# temp-stellwerk-laser-4-left.net
KiCad netlist of a schematic drawn in EAGLE
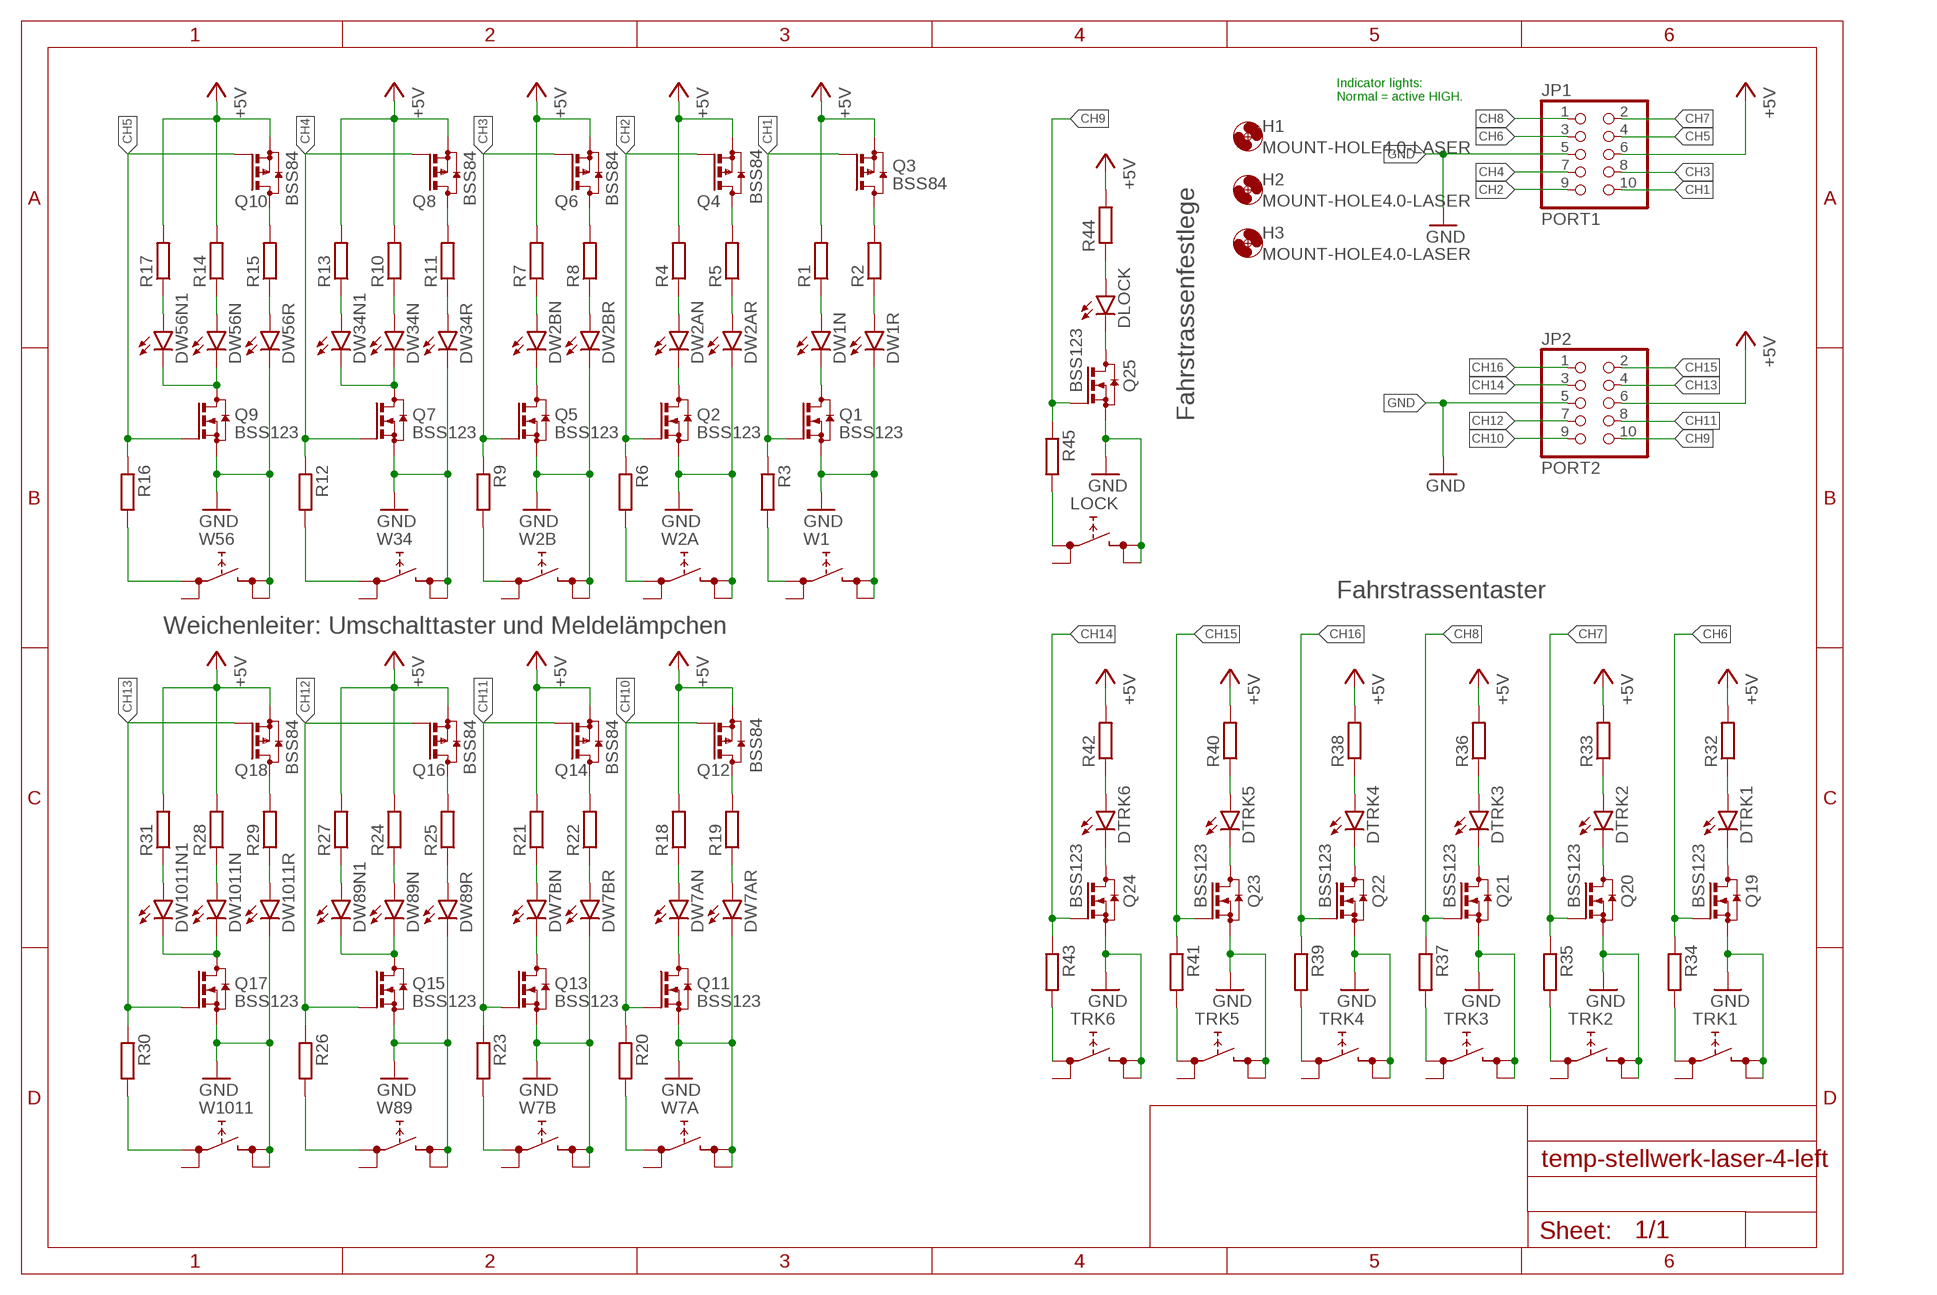
[diagram p0: schematic, sheet 1]

(export (version "E")
  (design (tool "Eeschema 10.0.6"))
  (components
    (comp (ref "DLOCK")
      (value "LEDCHIPLED_0805")
      (footprint "eagle-import:CHIPLED_0805")
      (libsource (lib "eagle-import") (part "LEDCHIPLED_0805"))
    )
    (comp (ref "DTRK1")
      (value "LEDCHIPLED_0805")
      (footprint "eagle-import:CHIPLED_0805")
      (libsource (lib "eagle-import") (part "LEDCHIPLED_0805"))
    )
    (comp (ref "DTRK2")
      (value "LEDCHIPLED_0805")
      (footprint "eagle-import:CHIPLED_0805")
      (libsource (lib "eagle-import") (part "LEDCHIPLED_0805"))
    )
    (comp (ref "DTRK3")
      (value "LEDCHIPLED_0805")
      (footprint "eagle-import:CHIPLED_0805")
      (libsource (lib "eagle-import") (part "LEDCHIPLED_0805"))
    )
    (comp (ref "DTRK4")
      (value "LEDCHIPLED_0805")
      (footprint "eagle-import:CHIPLED_0805")
      (libsource (lib "eagle-import") (part "LEDCHIPLED_0805"))
    )
    (comp (ref "DTRK5")
      (value "LEDCHIPLED_0805")
      (footprint "eagle-import:CHIPLED_0805")
      (libsource (lib "eagle-import") (part "LEDCHIPLED_0805"))
    )
    (comp (ref "DTRK6")
      (value "LEDCHIPLED_0805")
      (footprint "eagle-import:CHIPLED_0805")
      (libsource (lib "eagle-import") (part "LEDCHIPLED_0805"))
    )
    (comp (ref "DW1N")
      (value "LEDCHIPLED_0603")
      (footprint "eagle-import:CHIPLED_0603")
      (libsource (lib "eagle-import") (part "LEDCHIPLED_0603"))
    )
    (comp (ref "DW1R")
      (value "LEDCHIPLED_0603")
      (footprint "eagle-import:CHIPLED_0603")
      (libsource (lib "eagle-import") (part "LEDCHIPLED_0603"))
    )
    (comp (ref "DW2AN")
      (value "LEDCHIPLED_0603")
      (footprint "eagle-import:CHIPLED_0603")
      (libsource (lib "eagle-import") (part "LEDCHIPLED_0603"))
    )
    (comp (ref "DW2AR")
      (value "LEDCHIPLED_0603")
      (footprint "eagle-import:CHIPLED_0603")
      (libsource (lib "eagle-import") (part "LEDCHIPLED_0603"))
    )
    (comp (ref "DW2BN")
      (value "LEDCHIPLED_0805")
      (footprint "eagle-import:CHIPLED_0805")
      (libsource (lib "eagle-import") (part "LEDCHIPLED_0805"))
    )
    (comp (ref "DW2BR")
      (value "LEDCHIPLED_0805")
      (footprint "eagle-import:CHIPLED_0805")
      (libsource (lib "eagle-import") (part "LEDCHIPLED_0805"))
    )
    (comp (ref "DW7AN")
      (value "LEDCHIPLED_0603")
      (footprint "eagle-import:CHIPLED_0603")
      (libsource (lib "eagle-import") (part "LEDCHIPLED_0603"))
    )
    (comp (ref "DW7AR")
      (value "LEDCHIPLED_0603")
      (footprint "eagle-import:CHIPLED_0603")
      (libsource (lib "eagle-import") (part "LEDCHIPLED_0603"))
    )
    (comp (ref "DW7BN")
      (value "LEDCHIPLED_0805")
      (footprint "eagle-import:CHIPLED_0805")
      (libsource (lib "eagle-import") (part "LEDCHIPLED_0805"))
    )
    (comp (ref "DW7BR")
      (value "LEDCHIPLED_0805")
      (footprint "eagle-import:CHIPLED_0805")
      (libsource (lib "eagle-import") (part "LEDCHIPLED_0805"))
    )
    (comp (ref "DW34N")
      (value "LEDCHIPLED_0805")
      (footprint "eagle-import:CHIPLED_0805")
      (libsource (lib "eagle-import") (part "LEDCHIPLED_0805"))
    )
    (comp (ref "DW34N1")
      (value "LEDCHIPLED_0805")
      (footprint "eagle-import:CHIPLED_0805")
      (libsource (lib "eagle-import") (part "LEDCHIPLED_0805"))
    )
    (comp (ref "DW34R")
      (value "LEDCHIPLED_0805")
      (footprint "eagle-import:CHIPLED_0805")
      (libsource (lib "eagle-import") (part "LEDCHIPLED_0805"))
    )
    (comp (ref "DW56N")
      (value "LEDCHIPLED_0805")
      (footprint "eagle-import:CHIPLED_0805")
      (libsource (lib "eagle-import") (part "LEDCHIPLED_0805"))
    )
    (comp (ref "DW56N1")
      (value "LEDCHIPLED_0805")
      (footprint "eagle-import:CHIPLED_0805")
      (libsource (lib "eagle-import") (part "LEDCHIPLED_0805"))
    )
    (comp (ref "DW56R")
      (value "LEDCHIPLED_0805")
      (footprint "eagle-import:CHIPLED_0805")
      (libsource (lib "eagle-import") (part "LEDCHIPLED_0805"))
    )
    (comp (ref "DW89N")
      (value "LEDCHIPLED_0805")
      (footprint "eagle-import:CHIPLED_0805")
      (libsource (lib "eagle-import") (part "LEDCHIPLED_0805"))
    )
    (comp (ref "DW89N1")
      (value "LEDCHIPLED_0805")
      (footprint "eagle-import:CHIPLED_0805")
      (libsource (lib "eagle-import") (part "LEDCHIPLED_0805"))
    )
    (comp (ref "DW89R")
      (value "LEDCHIPLED_0805")
      (footprint "eagle-import:CHIPLED_0805")
      (libsource (lib "eagle-import") (part "LEDCHIPLED_0805"))
    )
    (comp (ref "DW1011N")
      (value "LEDCHIPLED_0805")
      (footprint "eagle-import:CHIPLED_0805")
      (libsource (lib "eagle-import") (part "LEDCHIPLED_0805"))
    )
    (comp (ref "DW1011N1")
      (value "LEDCHIPLED_0805")
      (footprint "eagle-import:CHIPLED_0805")
      (libsource (lib "eagle-import") (part "LEDCHIPLED_0805"))
    )
    (comp (ref "DW1011R")
      (value "LEDCHIPLED_0805")
      (footprint "eagle-import:CHIPLED_0805")
      (libsource (lib "eagle-import") (part "LEDCHIPLED_0805"))
    )
    (comp (ref "H1")
      (value "MOUNT-HOLE4.0-LASER")
      (footprint "eagle-import:MOUNT-HOLE-3.2-4.0-LASER")
      (libsource (lib "eagle-import") (part "MOUNT-HOLE4.0-LASER"))
    )
    (comp (ref "H2")
      (value "MOUNT-HOLE4.0-LASER")
      (footprint "eagle-import:MOUNT-HOLE-3.2-4.0-LASER")
      (libsource (lib "eagle-import") (part "MOUNT-HOLE4.0-LASER"))
    )
    (comp (ref "H3")
      (value "MOUNT-HOLE4.0-LASER")
      (footprint "eagle-import:MOUNT-HOLE-3.2-4.0-LASER")
      (libsource (lib "eagle-import") (part "MOUNT-HOLE4.0-LASER"))
    )
    (comp (ref "JP1")
      (value "PORT1")
      (footprint "eagle-import:CON10M")
      (libsource (lib "eagle-import") (part "PINHD-2X5CN"))
    )
    (comp (ref "JP2")
      (value "PORT2")
      (footprint "eagle-import:CON10M")
      (libsource (lib "eagle-import") (part "PINHD-2X5CN"))
    )
    (comp (ref "LOCK")
      (value "LOCK")
      (footprint "eagle-import:TACTSW-6X6-LASER")
      (libsource (lib "eagle-import") (part "TACTSW-6X6S"))
    )
    (comp (ref "Q1")
      (value "BSS123")
      (footprint "eagle-import:SOT23-NCH")
      (libsource (lib "eagle-import") (part "BSS123"))
    )
    (comp (ref "Q2")
      (value "BSS123")
      (footprint "eagle-import:SOT23-NCH")
      (libsource (lib "eagle-import") (part "BSS123"))
    )
    (comp (ref "Q3")
      (value "BSS84")
      (footprint "eagle-import:SOT23")
      (libsource (lib "eagle-import") (part "BSS84"))
    )
    (comp (ref "Q4")
      (value "BSS84")
      (footprint "eagle-import:SOT23")
      (libsource (lib "eagle-import") (part "BSS84"))
    )
    (comp (ref "Q5")
      (value "BSS123")
      (footprint "eagle-import:SOT23-NCH")
      (libsource (lib "eagle-import") (part "BSS123"))
    )
    (comp (ref "Q6")
      (value "BSS84")
      (footprint "eagle-import:SOT23")
      (libsource (lib "eagle-import") (part "BSS84"))
    )
    (comp (ref "Q7")
      (value "BSS123")
      (footprint "eagle-import:SOT23-NCH")
      (libsource (lib "eagle-import") (part "BSS123"))
    )
    (comp (ref "Q8")
      (value "BSS84")
      (footprint "eagle-import:SOT23")
      (libsource (lib "eagle-import") (part "BSS84"))
    )
    (comp (ref "Q9")
      (value "BSS123")
      (footprint "eagle-import:SOT23-NCH")
      (libsource (lib "eagle-import") (part "BSS123"))
    )
    (comp (ref "Q10")
      (value "BSS84")
      (footprint "eagle-import:SOT23")
      (libsource (lib "eagle-import") (part "BSS84"))
    )
    (comp (ref "Q11")
      (value "BSS123")
      (footprint "eagle-import:SOT23-NCH")
      (libsource (lib "eagle-import") (part "BSS123"))
    )
    (comp (ref "Q12")
      (value "BSS84")
      (footprint "eagle-import:SOT23")
      (libsource (lib "eagle-import") (part "BSS84"))
    )
    (comp (ref "Q13")
      (value "BSS123")
      (footprint "eagle-import:SOT23-NCH")
      (libsource (lib "eagle-import") (part "BSS123"))
    )
    (comp (ref "Q14")
      (value "BSS84")
      (footprint "eagle-import:SOT23")
      (libsource (lib "eagle-import") (part "BSS84"))
    )
    (comp (ref "Q15")
      (value "BSS123")
      (footprint "eagle-import:SOT23-NCH")
      (libsource (lib "eagle-import") (part "BSS123"))
    )
    (comp (ref "Q16")
      (value "BSS84")
      (footprint "eagle-import:SOT23")
      (libsource (lib "eagle-import") (part "BSS84"))
    )
    (comp (ref "Q17")
      (value "BSS123")
      (footprint "eagle-import:SOT23-NCH")
      (libsource (lib "eagle-import") (part "BSS123"))
    )
    (comp (ref "Q18")
      (value "BSS84")
      (footprint "eagle-import:SOT23")
      (libsource (lib "eagle-import") (part "BSS84"))
    )
    (comp (ref "Q19")
      (value "BSS123")
      (footprint "eagle-import:SOT23-NCH")
      (libsource (lib "eagle-import") (part "BSS123"))
    )
    (comp (ref "Q20")
      (value "BSS123")
      (footprint "eagle-import:SOT23-NCH")
      (libsource (lib "eagle-import") (part "BSS123"))
    )
    (comp (ref "Q21")
      (value "BSS123")
      (footprint "eagle-import:SOT23-NCH")
      (libsource (lib "eagle-import") (part "BSS123"))
    )
    (comp (ref "Q22")
      (value "BSS123")
      (footprint "eagle-import:SOT23-NCH")
      (libsource (lib "eagle-import") (part "BSS123"))
    )
    (comp (ref "Q23")
      (value "BSS123")
      (footprint "eagle-import:SOT23-NCH")
      (libsource (lib "eagle-import") (part "BSS123"))
    )
    (comp (ref "Q24")
      (value "BSS123")
      (footprint "eagle-import:SOT23-NCH")
      (libsource (lib "eagle-import") (part "BSS123"))
    )
    (comp (ref "Q25")
      (value "BSS123")
      (footprint "eagle-import:SOT23-NCH")
      (libsource (lib "eagle-import") (part "BSS123"))
    )
    (comp (ref "R1")
      (value "R-EU_R0805")
      (footprint "eagle-import:R0805")
      (libsource (lib "eagle-import") (part "R-EU_R0805"))
    )
    (comp (ref "R2")
      (value "R-EU_R0805")
      (footprint "eagle-import:R0805")
      (libsource (lib "eagle-import") (part "R-EU_R0805"))
    )
    (comp (ref "R3")
      (value "R-EU_R0805")
      (footprint "eagle-import:R0805")
      (libsource (lib "eagle-import") (part "R-EU_R0805"))
    )
    (comp (ref "R4")
      (value "R-EU_R0805")
      (footprint "eagle-import:R0805")
      (libsource (lib "eagle-import") (part "R-EU_R0805"))
    )
    (comp (ref "R5")
      (value "R-EU_R0805")
      (footprint "eagle-import:R0805")
      (libsource (lib "eagle-import") (part "R-EU_R0805"))
    )
    (comp (ref "R6")
      (value "R-EU_R0805")
      (footprint "eagle-import:R0805")
      (libsource (lib "eagle-import") (part "R-EU_R0805"))
    )
    (comp (ref "R7")
      (value "R-EU_R0805")
      (footprint "eagle-import:R0805")
      (libsource (lib "eagle-import") (part "R-EU_R0805"))
    )
    (comp (ref "R8")
      (value "R-EU_R0805")
      (footprint "eagle-import:R0805")
      (libsource (lib "eagle-import") (part "R-EU_R0805"))
    )
    (comp (ref "R9")
      (value "R-EU_R0805")
      (footprint "eagle-import:R0805")
      (libsource (lib "eagle-import") (part "R-EU_R0805"))
    )
    (comp (ref "R10")
      (value "R-EU_R0805")
      (footprint "eagle-import:R0805")
      (libsource (lib "eagle-import") (part "R-EU_R0805"))
    )
    (comp (ref "R11")
      (value "R-EU_R0805")
      (footprint "eagle-import:R0805")
      (libsource (lib "eagle-import") (part "R-EU_R0805"))
    )
    (comp (ref "R12")
      (value "R-EU_R0805")
      (footprint "eagle-import:R0805")
      (libsource (lib "eagle-import") (part "R-EU_R0805"))
    )
    (comp (ref "R13")
      (value "R-EU_R0805")
      (footprint "eagle-import:R0805")
      (libsource (lib "eagle-import") (part "R-EU_R0805"))
    )
    (comp (ref "R14")
      (value "R-EU_R0805")
      (footprint "eagle-import:R0805")
      (libsource (lib "eagle-import") (part "R-EU_R0805"))
    )
    (comp (ref "R15")
      (value "R-EU_R0805")
      (footprint "eagle-import:R0805")
      (libsource (lib "eagle-import") (part "R-EU_R0805"))
    )
    (comp (ref "R16")
      (value "R-EU_R0805")
      (footprint "eagle-import:R0805")
      (libsource (lib "eagle-import") (part "R-EU_R0805"))
    )
    (comp (ref "R17")
      (value "R-EU_R0805")
      (footprint "eagle-import:R0805")
      (libsource (lib "eagle-import") (part "R-EU_R0805"))
    )
    (comp (ref "R18")
      (value "R-EU_R0805")
      (footprint "eagle-import:R0805")
      (libsource (lib "eagle-import") (part "R-EU_R0805"))
    )
    (comp (ref "R19")
      (value "R-EU_R0805")
      (footprint "eagle-import:R0805")
      (libsource (lib "eagle-import") (part "R-EU_R0805"))
    )
    (comp (ref "R20")
      (value "R-EU_R0805")
      (footprint "eagle-import:R0805")
      (libsource (lib "eagle-import") (part "R-EU_R0805"))
    )
    (comp (ref "R21")
      (value "R-EU_R0805")
      (footprint "eagle-import:R0805")
      (libsource (lib "eagle-import") (part "R-EU_R0805"))
    )
    (comp (ref "R22")
      (value "R-EU_R0805")
      (footprint "eagle-import:R0805")
      (libsource (lib "eagle-import") (part "R-EU_R0805"))
    )
    (comp (ref "R23")
      (value "R-EU_R0805")
      (footprint "eagle-import:R0805")
      (libsource (lib "eagle-import") (part "R-EU_R0805"))
    )
    (comp (ref "R24")
      (value "R-EU_R0805")
      (footprint "eagle-import:R0805")
      (libsource (lib "eagle-import") (part "R-EU_R0805"))
    )
    (comp (ref "R25")
      (value "R-EU_R0805")
      (footprint "eagle-import:R0805")
      (libsource (lib "eagle-import") (part "R-EU_R0805"))
    )
    (comp (ref "R26")
      (value "R-EU_R0805")
      (footprint "eagle-import:R0805")
      (libsource (lib "eagle-import") (part "R-EU_R0805"))
    )
    (comp (ref "R27")
      (value "R-EU_R0805")
      (footprint "eagle-import:R0805")
      (libsource (lib "eagle-import") (part "R-EU_R0805"))
    )
    (comp (ref "R28")
      (value "R-EU_R0805")
      (footprint "eagle-import:R0805")
      (libsource (lib "eagle-import") (part "R-EU_R0805"))
    )
    (comp (ref "R29")
      (value "R-EU_R0805")
      (footprint "eagle-import:R0805")
      (libsource (lib "eagle-import") (part "R-EU_R0805"))
    )
    (comp (ref "R30")
      (value "R-EU_R0805")
      (footprint "eagle-import:R0805")
      (libsource (lib "eagle-import") (part "R-EU_R0805"))
    )
    (comp (ref "R31")
      (value "R-EU_R0805")
      (footprint "eagle-import:R0805")
      (libsource (lib "eagle-import") (part "R-EU_R0805"))
    )
    (comp (ref "R32")
      (value "R-EU_R0805")
      (footprint "eagle-import:R0805")
      (libsource (lib "eagle-import") (part "R-EU_R0805"))
    )
    (comp (ref "R33")
      (value "R-EU_R0805")
      (footprint "eagle-import:R0805")
      (libsource (lib "eagle-import") (part "R-EU_R0805"))
    )
    (comp (ref "R34")
      (value "R-EU_R0805")
      (footprint "eagle-import:R0805")
      (libsource (lib "eagle-import") (part "R-EU_R0805"))
    )
    (comp (ref "R35")
      (value "R-EU_R0805")
      (footprint "eagle-import:R0805")
      (libsource (lib "eagle-import") (part "R-EU_R0805"))
    )
    (comp (ref "R36")
      (value "R-EU_R0805")
      (footprint "eagle-import:R0805")
      (libsource (lib "eagle-import") (part "R-EU_R0805"))
    )
    (comp (ref "R37")
      (value "R-EU_R0805")
      (footprint "eagle-import:R0805")
      (libsource (lib "eagle-import") (part "R-EU_R0805"))
    )
    (comp (ref "R38")
      (value "R-EU_R0805")
      (footprint "eagle-import:R0805")
      (libsource (lib "eagle-import") (part "R-EU_R0805"))
    )
    (comp (ref "R39")
      (value "R-EU_R0805")
      (footprint "eagle-import:R0805")
      (libsource (lib "eagle-import") (part "R-EU_R0805"))
    )
    (comp (ref "R40")
      (value "R-EU_R0805")
      (footprint "eagle-import:R0805")
      (libsource (lib "eagle-import") (part "R-EU_R0805"))
    )
    (comp (ref "R41")
      (value "R-EU_R0805")
      (footprint "eagle-import:R0805")
      (libsource (lib "eagle-import") (part "R-EU_R0805"))
    )
    (comp (ref "R42")
      (value "R-EU_R0805")
      (footprint "eagle-import:R0805")
      (libsource (lib "eagle-import") (part "R-EU_R0805"))
    )
    (comp (ref "R43")
      (value "R-EU_R0805")
      (footprint "eagle-import:R0805")
      (libsource (lib "eagle-import") (part "R-EU_R0805"))
    )
    (comp (ref "R44")
      (value "R-EU_R0805")
      (footprint "eagle-import:R0805")
      (libsource (lib "eagle-import") (part "R-EU_R0805"))
    )
    (comp (ref "R45")
      (value "R-EU_R0805")
      (footprint "eagle-import:R0805")
      (libsource (lib "eagle-import") (part "R-EU_R0805"))
    )
    (comp (ref "TRK1")
      (value "TACTSW-6X6S")
      (footprint "eagle-import:TACTSW-6X6-LASER")
      (libsource (lib "eagle-import") (part "TACTSW-6X6S"))
    )
    (comp (ref "TRK2")
      (value "TACTSW-6X6S")
      (footprint "eagle-import:TACTSW-6X6-LASER")
      (libsource (lib "eagle-import") (part "TACTSW-6X6S"))
    )
    (comp (ref "TRK3")
      (value "TACTSW-6X6S")
      (footprint "eagle-import:TACTSW-6X6-LASER")
      (libsource (lib "eagle-import") (part "TACTSW-6X6S"))
    )
    (comp (ref "TRK4")
      (value "TACTSW-6X6S")
      (footprint "eagle-import:TACTSW-6X6-LASER")
      (libsource (lib "eagle-import") (part "TACTSW-6X6S"))
    )
    (comp (ref "TRK5")
      (value "TACTSW-6X6S")
      (footprint "eagle-import:TACTSW-6X6-LASER")
      (libsource (lib "eagle-import") (part "TACTSW-6X6S"))
    )
    (comp (ref "TRK6")
      (value "TACTSW-6X6S")
      (footprint "eagle-import:TACTSW-6X6-LASER")
      (libsource (lib "eagle-import") (part "TACTSW-6X6S"))
    )
    (comp (ref "W1")
      (value "W1")
      (footprint "eagle-import:TACTSW-6X6-LASER")
      (libsource (lib "eagle-import") (part "TACTSW-6X6S"))
    )
    (comp (ref "W2A")
      (value "TACTSW-6X6S")
      (footprint "eagle-import:TACTSW-6X6-LASER")
      (libsource (lib "eagle-import") (part "TACTSW-6X6S"))
    )
    (comp (ref "W2B")
      (value "TACTSW-6X6S")
      (footprint "eagle-import:TACTSW-6X6-LASER")
      (libsource (lib "eagle-import") (part "TACTSW-6X6S"))
    )
    (comp (ref "W7A")
      (value "TACTSW-6X6S")
      (footprint "eagle-import:TACTSW-6X6-LASER")
      (libsource (lib "eagle-import") (part "TACTSW-6X6S"))
    )
    (comp (ref "W7B")
      (value "TACTSW-6X6S")
      (footprint "eagle-import:TACTSW-6X6-LASER")
      (libsource (lib "eagle-import") (part "TACTSW-6X6S"))
    )
    (comp (ref "W34")
      (value "XOVER")
      (footprint "eagle-import:TACTSW-6X6-LASER")
      (libsource (lib "eagle-import") (part "TACTSW-6X6S"))
    )
    (comp (ref "W56")
      (value "XOVER")
      (footprint "eagle-import:TACTSW-6X6-LASER")
      (libsource (lib "eagle-import") (part "TACTSW-6X6S"))
    )
    (comp (ref "W89")
      (value "XOVER")
      (footprint "eagle-import:TACTSW-6X6-LASER")
      (libsource (lib "eagle-import") (part "TACTSW-6X6S"))
    )
    (comp (ref "W1011")
      (value "XOVER")
      (footprint "eagle-import:TACTSW-6X6-LASER")
      (libsource (lib "eagle-import") (part "TACTSW-6X6S"))
    )
  )
  (nets
    (net (code "1") (name "+5V") (class "Default")
      (node (ref "JP1") (pin "6") (pinfunction "6_6") (pintype "passive"))
      (node (ref "JP2") (pin "6") (pinfunction "6_6") (pintype "passive"))
      (node (ref "Q10") (pin "2") (pinfunction "S_2") (pintype "passive"))
      (node (ref "Q12") (pin "2") (pinfunction "S_2") (pintype "passive"))
      (node (ref "Q14") (pin "2") (pinfunction "S_2") (pintype "passive"))
      (node (ref "Q16") (pin "2") (pinfunction "S_2") (pintype "passive"))
      (node (ref "Q18") (pin "2") (pinfunction "S_2") (pintype "passive"))
      (node (ref "Q3") (pin "2") (pinfunction "S_2") (pintype "passive"))
      (node (ref "Q4") (pin "2") (pinfunction "S_2") (pintype "passive"))
      (node (ref "Q6") (pin "2") (pinfunction "S_2") (pintype "passive"))
      (node (ref "Q8") (pin "2") (pinfunction "S_2") (pintype "passive"))
      (node (ref "R1") (pin "2") (pinfunction "2_2") (pintype "passive"))
      (node (ref "R10") (pin "2") (pinfunction "2_2") (pintype "passive"))
      (node (ref "R13") (pin "2") (pinfunction "2_2") (pintype "passive"))
      (node (ref "R14") (pin "2") (pinfunction "2_2") (pintype "passive"))
      (node (ref "R17") (pin "2") (pinfunction "2_2") (pintype "passive"))
      (node (ref "R18") (pin "2") (pinfunction "2_2") (pintype "passive"))
      (node (ref "R21") (pin "2") (pinfunction "2_2") (pintype "passive"))
      (node (ref "R24") (pin "2") (pinfunction "2_2") (pintype "passive"))
      (node (ref "R27") (pin "2") (pinfunction "2_2") (pintype "passive"))
      (node (ref "R28") (pin "2") (pinfunction "2_2") (pintype "passive"))
      (node (ref "R31") (pin "2") (pinfunction "2_2") (pintype "passive"))
      (node (ref "R32") (pin "2") (pinfunction "2_2") (pintype "passive"))
      (node (ref "R33") (pin "2") (pinfunction "2_2") (pintype "passive"))
      (node (ref "R36") (pin "2") (pinfunction "2_2") (pintype "passive"))
      (node (ref "R38") (pin "2") (pinfunction "2_2") (pintype "passive"))
      (node (ref "R4") (pin "2") (pinfunction "2_2") (pintype "passive"))
      (node (ref "R40") (pin "2") (pinfunction "2_2") (pintype "passive"))
      (node (ref "R42") (pin "2") (pinfunction "2_2") (pintype "passive"))
      (node (ref "R44") (pin "2") (pinfunction "2_2") (pintype "passive"))
      (node (ref "R7") (pin "2") (pinfunction "2_2") (pintype "passive"))
    )
    (net (code "2") (name "CH1") (class "Default")
      (node (ref "JP1") (pin "10") (pinfunction "10_10") (pintype "passive"))
      (node (ref "Q1") (pin "1") (pinfunction "G_1") (pintype "passive"))
      (node (ref "Q3") (pin "1") (pinfunction "G_1") (pintype "passive"))
      (node (ref "R3") (pin "1") (pinfunction "1_1") (pintype "passive"))
    )
    (net (code "3") (name "CH2") (class "Default")
      (node (ref "JP1") (pin "9") (pinfunction "9_9") (pintype "passive"))
      (node (ref "Q2") (pin "1") (pinfunction "G_1") (pintype "passive"))
      (node (ref "Q4") (pin "1") (pinfunction "G_1") (pintype "passive"))
      (node (ref "R6") (pin "1") (pinfunction "1_1") (pintype "passive"))
    )
    (net (code "4") (name "CH3") (class "Default")
      (node (ref "JP1") (pin "8") (pinfunction "8_8") (pintype "passive"))
      (node (ref "Q5") (pin "1") (pinfunction "G_1") (pintype "passive"))
      (node (ref "Q6") (pin "1") (pinfunction "G_1") (pintype "passive"))
      (node (ref "R9") (pin "1") (pinfunction "1_1") (pintype "passive"))
    )
    (net (code "5") (name "CH4") (class "Default")
      (node (ref "JP1") (pin "7") (pinfunction "7_7") (pintype "passive"))
      (node (ref "Q7") (pin "1") (pinfunction "G_1") (pintype "passive"))
      (node (ref "Q8") (pin "1") (pinfunction "G_1") (pintype "passive"))
      (node (ref "R12") (pin "1") (pinfunction "1_1") (pintype "passive"))
    )
    (net (code "6") (name "CH5") (class "Default")
      (node (ref "JP1") (pin "4") (pinfunction "4_4") (pintype "passive"))
      (node (ref "Q10") (pin "1") (pinfunction "G_1") (pintype "passive"))
      (node (ref "Q9") (pin "1") (pinfunction "G_1") (pintype "passive"))
      (node (ref "R16") (pin "1") (pinfunction "1_1") (pintype "passive"))
    )
    (net (code "7") (name "CH6") (class "Default")
      (node (ref "JP1") (pin "3") (pinfunction "3_3") (pintype "passive"))
      (node (ref "Q19") (pin "1") (pinfunction "G_1") (pintype "passive"))
      (node (ref "R34") (pin "1") (pinfunction "1_1") (pintype "passive"))
    )
    (net (code "8") (name "CH7") (class "Default")
      (node (ref "JP1") (pin "2") (pinfunction "2_2") (pintype "passive"))
      (node (ref "Q20") (pin "1") (pinfunction "G_1") (pintype "passive"))
      (node (ref "R35") (pin "1") (pinfunction "1_1") (pintype "passive"))
    )
    (net (code "9") (name "CH8") (class "Default")
      (node (ref "JP1") (pin "1") (pinfunction "1_1") (pintype "passive"))
      (node (ref "Q21") (pin "1") (pinfunction "G_1") (pintype "passive"))
      (node (ref "R37") (pin "1") (pinfunction "1_1") (pintype "passive"))
    )
    (net (code "10") (name "CH9") (class "Default")
      (node (ref "JP2") (pin "10") (pinfunction "10_10") (pintype "passive"))
      (node (ref "Q25") (pin "1") (pinfunction "G_1") (pintype "passive"))
      (node (ref "R45") (pin "1") (pinfunction "1_1") (pintype "passive"))
    )
    (net (code "11") (name "CH10") (class "Default")
      (node (ref "JP2") (pin "9") (pinfunction "9_9") (pintype "passive"))
      (node (ref "Q11") (pin "1") (pinfunction "G_1") (pintype "passive"))
      (node (ref "Q12") (pin "1") (pinfunction "G_1") (pintype "passive"))
      (node (ref "R20") (pin "1") (pinfunction "1_1") (pintype "passive"))
    )
    (net (code "12") (name "CH11") (class "Default")
      (node (ref "JP2") (pin "8") (pinfunction "8_8") (pintype "passive"))
      (node (ref "Q13") (pin "1") (pinfunction "G_1") (pintype "passive"))
      (node (ref "Q14") (pin "1") (pinfunction "G_1") (pintype "passive"))
      (node (ref "R23") (pin "1") (pinfunction "1_1") (pintype "passive"))
    )
    (net (code "13") (name "CH12") (class "Default")
      (node (ref "JP2") (pin "7") (pinfunction "7_7") (pintype "passive"))
      (node (ref "Q15") (pin "1") (pinfunction "G_1") (pintype "passive"))
      (node (ref "Q16") (pin "1") (pinfunction "G_1") (pintype "passive"))
      (node (ref "R26") (pin "1") (pinfunction "1_1") (pintype "passive"))
    )
    (net (code "14") (name "CH13") (class "Default")
      (node (ref "JP2") (pin "4") (pinfunction "4_4") (pintype "passive"))
      (node (ref "Q17") (pin "1") (pinfunction "G_1") (pintype "passive"))
      (node (ref "Q18") (pin "1") (pinfunction "G_1") (pintype "passive"))
      (node (ref "R30") (pin "1") (pinfunction "1_1") (pintype "passive"))
    )
    (net (code "15") (name "CH14") (class "Default")
      (node (ref "JP2") (pin "3") (pinfunction "3_3") (pintype "passive"))
      (node (ref "Q24") (pin "1") (pinfunction "G_1") (pintype "passive"))
      (node (ref "R43") (pin "1") (pinfunction "1_1") (pintype "passive"))
    )
    (net (code "16") (name "CH15") (class "Default")
      (node (ref "JP2") (pin "2") (pinfunction "2_2") (pintype "passive"))
      (node (ref "Q23") (pin "1") (pinfunction "G_1") (pintype "passive"))
      (node (ref "R41") (pin "1") (pinfunction "1_1") (pintype "passive"))
    )
    (net (code "17") (name "CH16") (class "Default")
      (node (ref "JP2") (pin "1") (pinfunction "1_1") (pintype "passive"))
      (node (ref "Q22") (pin "1") (pinfunction "G_1") (pintype "passive"))
      (node (ref "R39") (pin "1") (pinfunction "1_1") (pintype "passive"))
    )
    (net (code "18") (name "GND") (class "Default")
      (node (ref "DW1011R") (pin "C") (pinfunction "C_C") (pintype "passive"))
      (node (ref "DW1R") (pin "C") (pinfunction "C_C") (pintype "passive"))
      (node (ref "DW2AR") (pin "C") (pinfunction "C_C") (pintype "passive"))
      (node (ref "DW2BR") (pin "C") (pinfunction "C_C") (pintype "passive"))
      (node (ref "DW34R") (pin "C") (pinfunction "C_C") (pintype "passive"))
      (node (ref "DW56R") (pin "C") (pinfunction "C_C") (pintype "passive"))
      (node (ref "DW7AR") (pin "C") (pinfunction "C_C") (pintype "passive"))
      (node (ref "DW7BR") (pin "C") (pinfunction "C_C") (pintype "passive"))
      (node (ref "DW89R") (pin "C") (pinfunction "C_C") (pintype "passive"))
      (node (ref "JP1") (pin "5") (pinfunction "5_5") (pintype "passive"))
      (node (ref "JP2") (pin "5") (pinfunction "5_5") (pintype "passive"))
      (node (ref "LOCK") (pin "3") (pinfunction "2.1_3") (pintype "passive"))
      (node (ref "LOCK") (pin "4") (pinfunction "2.2_4") (pintype "passive"))
      (node (ref "Q1") (pin "2") (pinfunction "S_2") (pintype "passive"))
      (node (ref "Q11") (pin "2") (pinfunction "S_2") (pintype "passive"))
      (node (ref "Q13") (pin "2") (pinfunction "S_2") (pintype "passive"))
      (node (ref "Q15") (pin "2") (pinfunction "S_2") (pintype "passive"))
      (node (ref "Q17") (pin "2") (pinfunction "S_2") (pintype "passive"))
      (node (ref "Q19") (pin "2") (pinfunction "S_2") (pintype "passive"))
      (node (ref "Q2") (pin "2") (pinfunction "S_2") (pintype "passive"))
      (node (ref "Q20") (pin "2") (pinfunction "S_2") (pintype "passive"))
      (node (ref "Q21") (pin "2") (pinfunction "S_2") (pintype "passive"))
      (node (ref "Q22") (pin "2") (pinfunction "S_2") (pintype "passive"))
      (node (ref "Q23") (pin "2") (pinfunction "S_2") (pintype "passive"))
      (node (ref "Q24") (pin "2") (pinfunction "S_2") (pintype "passive"))
      (node (ref "Q25") (pin "2") (pinfunction "S_2") (pintype "passive"))
      (node (ref "Q5") (pin "2") (pinfunction "S_2") (pintype "passive"))
      (node (ref "Q7") (pin "2") (pinfunction "S_2") (pintype "passive"))
      (node (ref "Q9") (pin "2") (pinfunction "S_2") (pintype "passive"))
      (node (ref "TRK1") (pin "3") (pinfunction "2.1_3") (pintype "passive"))
      (node (ref "TRK1") (pin "4") (pinfunction "2.2_4") (pintype "passive"))
      (node (ref "TRK2") (pin "3") (pinfunction "2.1_3") (pintype "passive"))
      (node (ref "TRK2") (pin "4") (pinfunction "2.2_4") (pintype "passive"))
      (node (ref "TRK3") (pin "3") (pinfunction "2.1_3") (pintype "passive"))
      (node (ref "TRK3") (pin "4") (pinfunction "2.2_4") (pintype "passive"))
      (node (ref "TRK4") (pin "3") (pinfunction "2.1_3") (pintype "passive"))
      (node (ref "TRK4") (pin "4") (pinfunction "2.2_4") (pintype "passive"))
      (node (ref "TRK5") (pin "3") (pinfunction "2.1_3") (pintype "passive"))
      (node (ref "TRK5") (pin "4") (pinfunction "2.2_4") (pintype "passive"))
      (node (ref "TRK6") (pin "3") (pinfunction "2.1_3") (pintype "passive"))
      (node (ref "TRK6") (pin "4") (pinfunction "2.2_4") (pintype "passive"))
      (node (ref "W1") (pin "3") (pinfunction "2.1_3") (pintype "passive"))
      (node (ref "W1") (pin "4") (pinfunction "2.2_4") (pintype "passive"))
      (node (ref "W1011") (pin "3") (pinfunction "2.1_3") (pintype "passive"))
      (node (ref "W1011") (pin "4") (pinfunction "2.2_4") (pintype "passive"))
      (node (ref "W2A") (pin "3") (pinfunction "2.1_3") (pintype "passive"))
      (node (ref "W2A") (pin "4") (pinfunction "2.2_4") (pintype "passive"))
      (node (ref "W2B") (pin "3") (pinfunction "2.1_3") (pintype "passive"))
      (node (ref "W2B") (pin "4") (pinfunction "2.2_4") (pintype "passive"))
      (node (ref "W34") (pin "3") (pinfunction "2.1_3") (pintype "passive"))
      (node (ref "W34") (pin "4") (pinfunction "2.2_4") (pintype "passive"))
      (node (ref "W56") (pin "3") (pinfunction "2.1_3") (pintype "passive"))
      (node (ref "W56") (pin "4") (pinfunction "2.2_4") (pintype "passive"))
      (node (ref "W7A") (pin "3") (pinfunction "2.1_3") (pintype "passive"))
      (node (ref "W7A") (pin "4") (pinfunction "2.2_4") (pintype "passive"))
      (node (ref "W7B") (pin "3") (pinfunction "2.1_3") (pintype "passive"))
      (node (ref "W7B") (pin "4") (pinfunction "2.2_4") (pintype "passive"))
      (node (ref "W89") (pin "3") (pinfunction "2.1_3") (pintype "passive"))
      (node (ref "W89") (pin "4") (pinfunction "2.2_4") (pintype "passive"))
    )
    (net (code "19") (name "Net-(DLOCK-PadA)") (class "Default")
      (node (ref "DLOCK") (pin "A") (pinfunction "A_A") (pintype "passive"))
      (node (ref "R44") (pin "1") (pinfunction "1_1") (pintype "passive"))
    )
    (net (code "20") (name "Net-(DTRK1-PadA)") (class "Default")
      (node (ref "DTRK1") (pin "A") (pinfunction "A_A") (pintype "passive"))
      (node (ref "R32") (pin "1") (pinfunction "1_1") (pintype "passive"))
    )
    (net (code "21") (name "Net-(DTRK2-PadA)") (class "Default")
      (node (ref "DTRK2") (pin "A") (pinfunction "A_A") (pintype "passive"))
      (node (ref "R33") (pin "1") (pinfunction "1_1") (pintype "passive"))
    )
    (net (code "22") (name "Net-(DTRK3-PadA)") (class "Default")
      (node (ref "DTRK3") (pin "A") (pinfunction "A_A") (pintype "passive"))
      (node (ref "R36") (pin "1") (pinfunction "1_1") (pintype "passive"))
    )
    (net (code "23") (name "Net-(DTRK4-PadA)") (class "Default")
      (node (ref "DTRK4") (pin "A") (pinfunction "A_A") (pintype "passive"))
      (node (ref "R38") (pin "1") (pinfunction "1_1") (pintype "passive"))
    )
    (net (code "24") (name "Net-(DTRK5-PadA)") (class "Default")
      (node (ref "DTRK5") (pin "A") (pinfunction "A_A") (pintype "passive"))
      (node (ref "R40") (pin "1") (pinfunction "1_1") (pintype "passive"))
    )
    (net (code "25") (name "Net-(DTRK6-PadA)") (class "Default")
      (node (ref "DTRK6") (pin "A") (pinfunction "A_A") (pintype "passive"))
      (node (ref "R42") (pin "1") (pinfunction "1_1") (pintype "passive"))
    )
    (net (code "26") (name "Net-(DW1N-PadA)") (class "Default")
      (node (ref "DW1N") (pin "A") (pinfunction "A_A") (pintype "passive"))
      (node (ref "R1") (pin "1") (pinfunction "1_1") (pintype "passive"))
    )
    (net (code "27") (name "Net-(DW1R-PadA)") (class "Default")
      (node (ref "DW1R") (pin "A") (pinfunction "A_A") (pintype "passive"))
      (node (ref "R2") (pin "1") (pinfunction "1_1") (pintype "passive"))
    )
    (net (code "28") (name "Net-(DW2AN-PadA)") (class "Default")
      (node (ref "DW2AN") (pin "A") (pinfunction "A_A") (pintype "passive"))
      (node (ref "R4") (pin "1") (pinfunction "1_1") (pintype "passive"))
    )
    (net (code "29") (name "Net-(DW2AR-PadA)") (class "Default")
      (node (ref "DW2AR") (pin "A") (pinfunction "A_A") (pintype "passive"))
      (node (ref "R5") (pin "1") (pinfunction "1_1") (pintype "passive"))
    )
    (net (code "30") (name "Net-(DW2BN-PadA)") (class "Default")
      (node (ref "DW2BN") (pin "A") (pinfunction "A_A") (pintype "passive"))
      (node (ref "R7") (pin "1") (pinfunction "1_1") (pintype "passive"))
    )
    (net (code "31") (name "Net-(DW2BR-PadA)") (class "Default")
      (node (ref "DW2BR") (pin "A") (pinfunction "A_A") (pintype "passive"))
      (node (ref "R8") (pin "1") (pinfunction "1_1") (pintype "passive"))
    )
    (net (code "32") (name "Net-(DW7AN-PadA)") (class "Default")
      (node (ref "DW7AN") (pin "A") (pinfunction "A_A") (pintype "passive"))
      (node (ref "R18") (pin "1") (pinfunction "1_1") (pintype "passive"))
    )
    (net (code "33") (name "Net-(DW7AR-PadA)") (class "Default")
      (node (ref "DW7AR") (pin "A") (pinfunction "A_A") (pintype "passive"))
      (node (ref "R19") (pin "1") (pinfunction "1_1") (pintype "passive"))
    )
    (net (code "34") (name "Net-(DW7BN-PadA)") (class "Default")
      (node (ref "DW7BN") (pin "A") (pinfunction "A_A") (pintype "passive"))
      (node (ref "R21") (pin "1") (pinfunction "1_1") (pintype "passive"))
    )
    (net (code "35") (name "Net-(DW7BR-PadA)") (class "Default")
      (node (ref "DW7BR") (pin "A") (pinfunction "A_A") (pintype "passive"))
      (node (ref "R22") (pin "1") (pinfunction "1_1") (pintype "passive"))
    )
    (net (code "36") (name "Net-(DW34N-PadA)") (class "Default")
      (node (ref "DW34N") (pin "A") (pinfunction "A_A") (pintype "passive"))
      (node (ref "R10") (pin "1") (pinfunction "1_1") (pintype "passive"))
    )
    (net (code "37") (name "Net-(DW34N1-PadA)") (class "Default")
      (node (ref "DW34N1") (pin "A") (pinfunction "A_A") (pintype "passive"))
      (node (ref "R13") (pin "1") (pinfunction "1_1") (pintype "passive"))
    )
    (net (code "38") (name "Net-(DW34R-PadA)") (class "Default")
      (node (ref "DW34R") (pin "A") (pinfunction "A_A") (pintype "passive"))
      (node (ref "R11") (pin "1") (pinfunction "1_1") (pintype "passive"))
    )
    (net (code "39") (name "Net-(DW56N-PadA)") (class "Default")
      (node (ref "DW56N") (pin "A") (pinfunction "A_A") (pintype "passive"))
      (node (ref "R14") (pin "1") (pinfunction "1_1") (pintype "passive"))
    )
    (net (code "40") (name "Net-(DW56N1-PadA)") (class "Default")
      (node (ref "DW56N1") (pin "A") (pinfunction "A_A") (pintype "passive"))
      (node (ref "R17") (pin "1") (pinfunction "1_1") (pintype "passive"))
    )
    (net (code "41") (name "Net-(DW56R-PadA)") (class "Default")
      (node (ref "DW56R") (pin "A") (pinfunction "A_A") (pintype "passive"))
      (node (ref "R15") (pin "1") (pinfunction "1_1") (pintype "passive"))
    )
    (net (code "42") (name "Net-(DW89N-PadA)") (class "Default")
      (node (ref "DW89N") (pin "A") (pinfunction "A_A") (pintype "passive"))
      (node (ref "R24") (pin "1") (pinfunction "1_1") (pintype "passive"))
    )
    (net (code "43") (name "Net-(DW89N1-PadA)") (class "Default")
      (node (ref "DW89N1") (pin "A") (pinfunction "A_A") (pintype "passive"))
      (node (ref "R27") (pin "1") (pinfunction "1_1") (pintype "passive"))
    )
    (net (code "44") (name "Net-(DW89R-PadA)") (class "Default")
      (node (ref "DW89R") (pin "A") (pinfunction "A_A") (pintype "passive"))
      (node (ref "R25") (pin "1") (pinfunction "1_1") (pintype "passive"))
    )
    (net (code "45") (name "Net-(DW1011N-PadA)") (class "Default")
      (node (ref "DW1011N") (pin "A") (pinfunction "A_A") (pintype "passive"))
      (node (ref "R28") (pin "1") (pinfunction "1_1") (pintype "passive"))
    )
    (net (code "46") (name "Net-(DW1011N1-PadA)") (class "Default")
      (node (ref "DW1011N1") (pin "A") (pinfunction "A_A") (pintype "passive"))
      (node (ref "R31") (pin "1") (pinfunction "1_1") (pintype "passive"))
    )
    (net (code "47") (name "Net-(DW1011R-PadA)") (class "Default")
      (node (ref "DW1011R") (pin "A") (pinfunction "A_A") (pintype "passive"))
      (node (ref "R29") (pin "1") (pinfunction "1_1") (pintype "passive"))
    )
    (net (code "48") (name "Net-(LOCK-1.1)") (class "Default")
      (node (ref "LOCK") (pin "1") (pinfunction "1.1_1") (pintype "passive"))
      (node (ref "R45") (pin "2") (pinfunction "2_2") (pintype "passive"))
    )
    (net (code "49") (name "Net-(Q1-D)") (class "Default")
      (node (ref "DW1N") (pin "C") (pinfunction "C_C") (pintype "passive"))
      (node (ref "Q1") (pin "3") (pinfunction "D_3") (pintype "passive"))
    )
    (net (code "50") (name "Net-(Q2-D)") (class "Default")
      (node (ref "DW2AN") (pin "C") (pinfunction "C_C") (pintype "passive"))
      (node (ref "Q2") (pin "3") (pinfunction "D_3") (pintype "passive"))
    )
    (net (code "51") (name "Net-(Q3-D)") (class "Default")
      (node (ref "Q3") (pin "3") (pinfunction "D_3") (pintype "passive"))
      (node (ref "R2") (pin "2") (pinfunction "2_2") (pintype "passive"))
    )
    (net (code "52") (name "Net-(Q4-D)") (class "Default")
      (node (ref "Q4") (pin "3") (pinfunction "D_3") (pintype "passive"))
      (node (ref "R5") (pin "2") (pinfunction "2_2") (pintype "passive"))
    )
    (net (code "53") (name "Net-(Q5-D)") (class "Default")
      (node (ref "DW2BN") (pin "C") (pinfunction "C_C") (pintype "passive"))
      (node (ref "Q5") (pin "3") (pinfunction "D_3") (pintype "passive"))
    )
    (net (code "54") (name "Net-(Q6-D)") (class "Default")
      (node (ref "Q6") (pin "3") (pinfunction "D_3") (pintype "passive"))
      (node (ref "R8") (pin "2") (pinfunction "2_2") (pintype "passive"))
    )
    (net (code "55") (name "Net-(Q7-D)") (class "Default")
      (node (ref "DW34N") (pin "C") (pinfunction "C_C") (pintype "passive"))
      (node (ref "DW34N1") (pin "C") (pinfunction "C_C") (pintype "passive"))
      (node (ref "Q7") (pin "3") (pinfunction "D_3") (pintype "passive"))
    )
    (net (code "56") (name "Net-(Q8-D)") (class "Default")
      (node (ref "Q8") (pin "3") (pinfunction "D_3") (pintype "passive"))
      (node (ref "R11") (pin "2") (pinfunction "2_2") (pintype "passive"))
    )
    (net (code "57") (name "Net-(Q9-D)") (class "Default")
      (node (ref "DW56N") (pin "C") (pinfunction "C_C") (pintype "passive"))
      (node (ref "DW56N1") (pin "C") (pinfunction "C_C") (pintype "passive"))
      (node (ref "Q9") (pin "3") (pinfunction "D_3") (pintype "passive"))
    )
    (net (code "58") (name "Net-(Q10-D)") (class "Default")
      (node (ref "Q10") (pin "3") (pinfunction "D_3") (pintype "passive"))
      (node (ref "R15") (pin "2") (pinfunction "2_2") (pintype "passive"))
    )
    (net (code "59") (name "Net-(Q11-D)") (class "Default")
      (node (ref "DW7AN") (pin "C") (pinfunction "C_C") (pintype "passive"))
      (node (ref "Q11") (pin "3") (pinfunction "D_3") (pintype "passive"))
    )
    (net (code "60") (name "Net-(Q12-D)") (class "Default")
      (node (ref "Q12") (pin "3") (pinfunction "D_3") (pintype "passive"))
      (node (ref "R19") (pin "2") (pinfunction "2_2") (pintype "passive"))
    )
    (net (code "61") (name "Net-(Q13-D)") (class "Default")
      (node (ref "DW7BN") (pin "C") (pinfunction "C_C") (pintype "passive"))
      (node (ref "Q13") (pin "3") (pinfunction "D_3") (pintype "passive"))
    )
    (net (code "62") (name "Net-(Q14-D)") (class "Default")
      (node (ref "Q14") (pin "3") (pinfunction "D_3") (pintype "passive"))
      (node (ref "R22") (pin "2") (pinfunction "2_2") (pintype "passive"))
    )
    (net (code "63") (name "Net-(Q15-D)") (class "Default")
      (node (ref "DW89N") (pin "C") (pinfunction "C_C") (pintype "passive"))
      (node (ref "DW89N1") (pin "C") (pinfunction "C_C") (pintype "passive"))
      (node (ref "Q15") (pin "3") (pinfunction "D_3") (pintype "passive"))
    )
    (net (code "64") (name "Net-(Q16-D)") (class "Default")
      (node (ref "Q16") (pin "3") (pinfunction "D_3") (pintype "passive"))
      (node (ref "R25") (pin "2") (pinfunction "2_2") (pintype "passive"))
    )
    (net (code "65") (name "Net-(Q17-D)") (class "Default")
      (node (ref "DW1011N") (pin "C") (pinfunction "C_C") (pintype "passive"))
      (node (ref "DW1011N1") (pin "C") (pinfunction "C_C") (pintype "passive"))
      (node (ref "Q17") (pin "3") (pinfunction "D_3") (pintype "passive"))
    )
    (net (code "66") (name "Net-(Q18-D)") (class "Default")
      (node (ref "Q18") (pin "3") (pinfunction "D_3") (pintype "passive"))
      (node (ref "R29") (pin "2") (pinfunction "2_2") (pintype "passive"))
    )
    (net (code "67") (name "Net-(Q19-D)") (class "Default")
      (node (ref "DTRK1") (pin "C") (pinfunction "C_C") (pintype "passive"))
      (node (ref "Q19") (pin "3") (pinfunction "D_3") (pintype "passive"))
    )
    (net (code "68") (name "Net-(Q20-D)") (class "Default")
      (node (ref "DTRK2") (pin "C") (pinfunction "C_C") (pintype "passive"))
      (node (ref "Q20") (pin "3") (pinfunction "D_3") (pintype "passive"))
    )
    (net (code "69") (name "Net-(Q21-D)") (class "Default")
      (node (ref "DTRK3") (pin "C") (pinfunction "C_C") (pintype "passive"))
      (node (ref "Q21") (pin "3") (pinfunction "D_3") (pintype "passive"))
    )
    (net (code "70") (name "Net-(Q22-D)") (class "Default")
      (node (ref "DTRK4") (pin "C") (pinfunction "C_C") (pintype "passive"))
      (node (ref "Q22") (pin "3") (pinfunction "D_3") (pintype "passive"))
    )
    (net (code "71") (name "Net-(Q23-D)") (class "Default")
      (node (ref "DTRK5") (pin "C") (pinfunction "C_C") (pintype "passive"))
      (node (ref "Q23") (pin "3") (pinfunction "D_3") (pintype "passive"))
    )
    (net (code "72") (name "Net-(Q24-D)") (class "Default")
      (node (ref "DTRK6") (pin "C") (pinfunction "C_C") (pintype "passive"))
      (node (ref "Q24") (pin "3") (pinfunction "D_3") (pintype "passive"))
    )
    (net (code "73") (name "Net-(Q25-D)") (class "Default")
      (node (ref "DLOCK") (pin "C") (pinfunction "C_C") (pintype "passive"))
      (node (ref "Q25") (pin "3") (pinfunction "D_3") (pintype "passive"))
    )
    (net (code "74") (name "Net-(TRK1-1.1)") (class "Default")
      (node (ref "R34") (pin "2") (pinfunction "2_2") (pintype "passive"))
      (node (ref "TRK1") (pin "1") (pinfunction "1.1_1") (pintype "passive"))
    )
    (net (code "75") (name "Net-(TRK2-1.1)") (class "Default")
      (node (ref "R35") (pin "2") (pinfunction "2_2") (pintype "passive"))
      (node (ref "TRK2") (pin "1") (pinfunction "1.1_1") (pintype "passive"))
    )
    (net (code "76") (name "Net-(TRK3-1.1)") (class "Default")
      (node (ref "R37") (pin "2") (pinfunction "2_2") (pintype "passive"))
      (node (ref "TRK3") (pin "1") (pinfunction "1.1_1") (pintype "passive"))
    )
    (net (code "77") (name "Net-(TRK4-1.1)") (class "Default")
      (node (ref "R39") (pin "2") (pinfunction "2_2") (pintype "passive"))
      (node (ref "TRK4") (pin "1") (pinfunction "1.1_1") (pintype "passive"))
    )
    (net (code "78") (name "Net-(TRK5-1.1)") (class "Default")
      (node (ref "R41") (pin "2") (pinfunction "2_2") (pintype "passive"))
      (node (ref "TRK5") (pin "1") (pinfunction "1.1_1") (pintype "passive"))
    )
    (net (code "79") (name "Net-(TRK6-1.1)") (class "Default")
      (node (ref "R43") (pin "2") (pinfunction "2_2") (pintype "passive"))
      (node (ref "TRK6") (pin "1") (pinfunction "1.1_1") (pintype "passive"))
    )
    (net (code "80") (name "Net-(W1-1.1)") (class "Default")
      (node (ref "R3") (pin "2") (pinfunction "2_2") (pintype "passive"))
      (node (ref "W1") (pin "1") (pinfunction "1.1_1") (pintype "passive"))
    )
    (net (code "81") (name "Net-(W2A-1.1)") (class "Default")
      (node (ref "R6") (pin "2") (pinfunction "2_2") (pintype "passive"))
      (node (ref "W2A") (pin "1") (pinfunction "1.1_1") (pintype "passive"))
    )
    (net (code "82") (name "Net-(W2B-1.1)") (class "Default")
      (node (ref "R9") (pin "2") (pinfunction "2_2") (pintype "passive"))
      (node (ref "W2B") (pin "1") (pinfunction "1.1_1") (pintype "passive"))
    )
    (net (code "83") (name "Net-(W7A-1.1)") (class "Default")
      (node (ref "R20") (pin "2") (pinfunction "2_2") (pintype "passive"))
      (node (ref "W7A") (pin "1") (pinfunction "1.1_1") (pintype "passive"))
    )
    (net (code "84") (name "Net-(W7B-1.1)") (class "Default")
      (node (ref "R23") (pin "2") (pinfunction "2_2") (pintype "passive"))
      (node (ref "W7B") (pin "1") (pinfunction "1.1_1") (pintype "passive"))
    )
    (net (code "85") (name "Net-(W34-1.1)") (class "Default")
      (node (ref "R12") (pin "2") (pinfunction "2_2") (pintype "passive"))
      (node (ref "W34") (pin "1") (pinfunction "1.1_1") (pintype "passive"))
    )
    (net (code "86") (name "Net-(W56-1.1)") (class "Default")
      (node (ref "R16") (pin "2") (pinfunction "2_2") (pintype "passive"))
      (node (ref "W56") (pin "1") (pinfunction "1.1_1") (pintype "passive"))
    )
    (net (code "87") (name "Net-(W89-1.1)") (class "Default")
      (node (ref "R26") (pin "2") (pinfunction "2_2") (pintype "passive"))
      (node (ref "W89") (pin "1") (pinfunction "1.1_1") (pintype "passive"))
    )
    (net (code "88") (name "Net-(W1011-1.1)") (class "Default")
      (node (ref "R30") (pin "2") (pinfunction "2_2") (pintype "passive"))
      (node (ref "W1011") (pin "1") (pinfunction "1.1_1") (pintype "passive"))
    )
    (net (code "89") (name "unconnected-(LOCK-1.2-Pad2)") (class "Default")
      (node (ref "LOCK") (pin "2") (pinfunction "1.2_2") (pintype "passive"))
    )
    (net (code "90") (name "unconnected-(TRK1-1.2-Pad2)") (class "Default")
      (node (ref "TRK1") (pin "2") (pinfunction "1.2_2") (pintype "passive"))
    )
    (net (code "91") (name "unconnected-(TRK2-1.2-Pad2)") (class "Default")
      (node (ref "TRK2") (pin "2") (pinfunction "1.2_2") (pintype "passive"))
    )
    (net (code "92") (name "unconnected-(TRK3-1.2-Pad2)") (class "Default")
      (node (ref "TRK3") (pin "2") (pinfunction "1.2_2") (pintype "passive"))
    )
    (net (code "93") (name "unconnected-(TRK4-1.2-Pad2)") (class "Default")
      (node (ref "TRK4") (pin "2") (pinfunction "1.2_2") (pintype "passive"))
    )
    (net (code "94") (name "unconnected-(TRK5-1.2-Pad2)") (class "Default")
      (node (ref "TRK5") (pin "2") (pinfunction "1.2_2") (pintype "passive"))
    )
    (net (code "95") (name "unconnected-(TRK6-1.2-Pad2)") (class "Default")
      (node (ref "TRK6") (pin "2") (pinfunction "1.2_2") (pintype "passive"))
    )
    (net (code "96") (name "unconnected-(W1-1.2-Pad2)") (class "Default")
      (node (ref "W1") (pin "2") (pinfunction "1.2_2") (pintype "passive"))
    )
    (net (code "97") (name "unconnected-(W2A-1.2-Pad2)") (class "Default")
      (node (ref "W2A") (pin "2") (pinfunction "1.2_2") (pintype "passive"))
    )
    (net (code "98") (name "unconnected-(W2B-1.2-Pad2)") (class "Default")
      (node (ref "W2B") (pin "2") (pinfunction "1.2_2") (pintype "passive"))
    )
    (net (code "99") (name "unconnected-(W7A-1.2-Pad2)") (class "Default")
      (node (ref "W7A") (pin "2") (pinfunction "1.2_2") (pintype "passive"))
    )
    (net (code "100") (name "unconnected-(W7B-1.2-Pad2)") (class "Default")
      (node (ref "W7B") (pin "2") (pinfunction "1.2_2") (pintype "passive"))
    )
    (net (code "101") (name "unconnected-(W34-1.2-Pad2)") (class "Default")
      (node (ref "W34") (pin "2") (pinfunction "1.2_2") (pintype "passive"))
    )
    (net (code "102") (name "unconnected-(W56-1.2-Pad2)") (class "Default")
      (node (ref "W56") (pin "2") (pinfunction "1.2_2") (pintype "passive"))
    )
    (net (code "103") (name "unconnected-(W89-1.2-Pad2)") (class "Default")
      (node (ref "W89") (pin "2") (pinfunction "1.2_2") (pintype "passive"))
    )
    (net (code "104") (name "unconnected-(W1011-1.2-Pad2)") (class "Default")
      (node (ref "W1011") (pin "2") (pinfunction "1.2_2") (pintype "passive"))
    )
  )
)
